# smart-bike-light.net
KiCad netlist of a schematic drawn in EAGLE
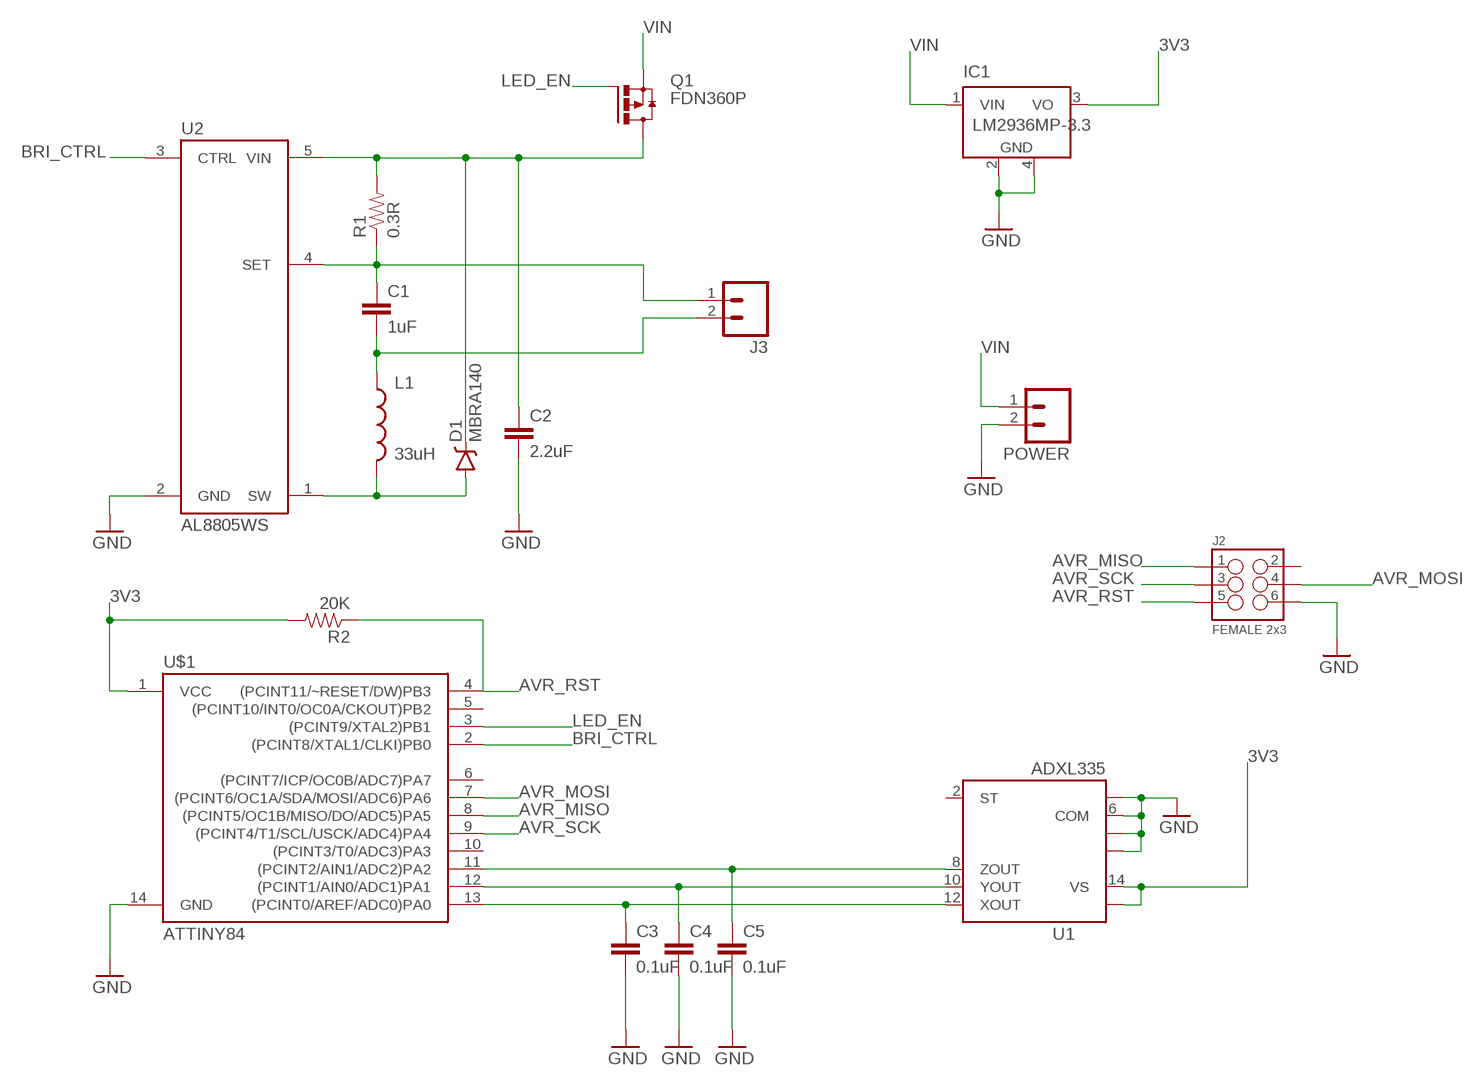
[diagram p0: schematic, sheet 1]

(export (version "E")
  (design (tool "Eeschema 10.0.6"))
  (components
    (comp (ref "C1")
      (value "1uF")
      (footprint "eagle-import:0603-CAP")
      (libsource (lib "eagle-import") (part "CAP0603-CAP"))
    )
    (comp (ref "C2")
      (value "2.2uF")
      (footprint "eagle-import:0603-CAP")
      (libsource (lib "eagle-import") (part "CAP0603-CAP"))
    )
    (comp (ref "C3")
      (value "0.1uF")
      (footprint "eagle-import:0603-CAP")
      (libsource (lib "eagle-import") (part "0.1UF-25V-5%(0603)"))
    )
    (comp (ref "C4")
      (value "0.1uF")
      (footprint "eagle-import:0603-CAP")
      (libsource (lib "eagle-import") (part "0.1UF-25V-5%(0603)"))
    )
    (comp (ref "C5")
      (value "0.1uF")
      (footprint "eagle-import:0603-CAP")
      (libsource (lib "eagle-import") (part "0.1UF-25V-5%(0603)"))
    )
    (comp (ref "D1")
      (value "MBRA140")
      (footprint "eagle-import:SMA-DIODE")
      (libsource (lib "eagle-import") (part "MBRA140"))
    )
    (comp (ref "IC1")
      (value "LM2936MP-3.3")
      (footprint "eagle-import:SOT223")
      (fields (field (name "MF") "NATIONAL SEMICONDUCTOR") (field (name "MPN") "LM2936MP-3.3/NOPB"))
      (libsource (lib "eagle-import") (part "LM2936MP?-3.3"))
    )
    (comp (ref "J2")
      (value "FEMALE 2x3")
      (footprint "eagle-import:2X3")
      (libsource (lib "eagle-import") (part "M03X2FEMALE"))
    )
    (comp (ref "J3")
      (value "M02PTH")
      (footprint "eagle-import:1X02")
      (libsource (lib "eagle-import") (part "M02PTH"))
    )
    (comp (ref "L1")
      (value "33uH")
      (footprint "eagle-import:SRN6045")
      (libsource (lib "eagle-import") (part "INDUCTORBOURNS_SRN6045"))
    )
    (comp (ref "POWER")
      (value "M02PTH")
      (footprint "eagle-import:1X02")
      (libsource (lib "eagle-import") (part "M02PTH"))
    )
    (comp (ref "Q1")
      (value "FDN360P")
      (footprint "eagle-import:SUPER-SOT3")
      (libsource (lib "eagle-import") (part "FDN360P"))
    )
    (comp (ref "R1")
      (value "0.3R")
      (footprint "eagle-import:0603-RES")
      (libsource (lib "eagle-import") (part "RESISTOR0603"))
    )
    (comp (ref "R2")
      (value "20K")
      (footprint "eagle-import:0603-RES")
      (libsource (lib "eagle-import") (part "RESISTOR0603"))
    )
    (comp (ref "U$1")
      (value "ATTINY84")
      (footprint "eagle-import:SO14")
      (libsource (lib "eagle-import") (part "ATTINY84"))
    )
    (comp (ref "U1")
      (value "ADXL335")
      (footprint "eagle-import:LFCSP-16")
      (libsource (lib "eagle-import") (part "ADXL335"))
    )
    (comp (ref "U2")
      (value "AL8805WS")
      (footprint "eagle-import:SOT23-5")
      (libsource (lib "eagle-import") (part "AL8805"))
    )
  )
  (nets
    (net (code "1") (name "/3V3") (class "Default")
      (node (ref "IC1") (pin "3") (pinfunction "VO_3") (pintype "passive"))
      (node (ref "R2") (pin "2") (pinfunction "2_2") (pintype "passive"))
      (node (ref "U$1") (pin "1") (pinfunction "VCC_1") (pintype "bidirectional"))
      (node (ref "U1") (pin "14") (pinfunction "VS_14") (pintype "bidirectional"))
      (node (ref "U1") (pin "15") (pinfunction "VS_15") (pintype "bidirectional"))
    )
    (net (code "2") (name "/AVR_MISO") (class "Default")
      (node (ref "J2") (pin "1") (pinfunction "1_1") (pintype "bidirectional"))
      (node (ref "U$1") (pin "8") (pinfunction "(PCINT5/OC1B/MISO/DO/ADC5)PA5_8") (pintype "bidirectional"))
    )
    (net (code "3") (name "/AVR_MOSI") (class "Default")
      (node (ref "J2") (pin "4") (pinfunction "4_4") (pintype "bidirectional"))
      (node (ref "U$1") (pin "7") (pinfunction "(PCINT6/OC1A/SDA/MOSI/ADC6)PA6_7") (pintype "bidirectional"))
    )
    (net (code "4") (name "/AVR_RST") (class "Default")
      (node (ref "J2") (pin "5") (pinfunction "5_5") (pintype "bidirectional"))
      (node (ref "R2") (pin "1") (pinfunction "1_1") (pintype "passive"))
      (node (ref "U$1") (pin "4") (pinfunction "(PCINT11/~{RESET/DW})PB3_4") (pintype "bidirectional"))
    )
    (net (code "5") (name "/AVR_SCK") (class "Default")
      (node (ref "J2") (pin "3") (pinfunction "3_3") (pintype "bidirectional"))
      (node (ref "U$1") (pin "9") (pinfunction "(PCINT4/T1/SCL/USCK/ADC4)PA4_9") (pintype "bidirectional"))
    )
    (net (code "6") (name "/BRI_CTRL") (class "Default")
      (node (ref "U$1") (pin "2") (pinfunction "(PCINT8/XTAL1/CLKI)PB0_2") (pintype "bidirectional"))
      (node (ref "U2") (pin "3") (pinfunction "CTRL_3") (pintype "bidirectional"))
    )
    (net (code "7") (name "/LED_EN") (class "Default")
      (node (ref "Q1") (pin "1") (pinfunction "G_1") (pintype "passive"))
      (node (ref "U$1") (pin "3") (pinfunction "(PCINT9/XTAL2)PB1_3") (pintype "bidirectional"))
    )
    (net (code "8") (name "/VIN") (class "Default")
      (node (ref "IC1") (pin "1") (pinfunction "VIN_1") (pintype "input"))
      (node (ref "POWER") (pin "1") (pinfunction "1_1") (pintype "passive"))
      (node (ref "Q1") (pin "2") (pinfunction "S_2") (pintype "passive"))
    )
    (net (code "9") (name "GND") (class "Default")
      (node (ref "C2") (pin "2") (pinfunction "2_2") (pintype "passive"))
      (node (ref "C3") (pin "2") (pinfunction "2_2") (pintype "passive"))
      (node (ref "C4") (pin "2") (pinfunction "2_2") (pintype "passive"))
      (node (ref "C5") (pin "2") (pinfunction "2_2") (pintype "passive"))
      (node (ref "IC1") (pin "2") (pinfunction "GND_2") (pintype "passive"))
      (node (ref "IC1") (pin "4") (pinfunction "GND_4") (pintype "passive"))
      (node (ref "J2") (pin "6") (pinfunction "6_6") (pintype "bidirectional"))
      (node (ref "POWER") (pin "2") (pinfunction "2_2") (pintype "passive"))
      (node (ref "U$1") (pin "14") (pinfunction "GND_14") (pintype "bidirectional"))
      (node (ref "U1") (pin "3") (pinfunction "COM_3") (pintype "bidirectional"))
      (node (ref "U1") (pin "5") (pinfunction "COM_5") (pintype "bidirectional"))
      (node (ref "U1") (pin "6") (pinfunction "COM_6") (pintype "bidirectional"))
      (node (ref "U1") (pin "7") (pinfunction "COM_7") (pintype "bidirectional"))
      (node (ref "U2") (pin "2") (pinfunction "GND_2") (pintype "bidirectional"))
    )
    (net (code "10") (name "Net-(C1-Pad2)") (class "Default")
      (node (ref "C1") (pin "2") (pinfunction "2_2") (pintype "passive"))
      (node (ref "J3") (pin "2") (pinfunction "2_2") (pintype "passive"))
      (node (ref "L1") (pin "1") (pinfunction "1_1") (pintype "passive"))
    )
    (net (code "11") (name "Net-(Q1-D)") (class "Default")
      (node (ref "C2") (pin "1") (pinfunction "1_1") (pintype "passive"))
      (node (ref "D1") (pin "C") (pinfunction "C_C") (pintype "passive"))
      (node (ref "Q1") (pin "3") (pinfunction "D_3") (pintype "passive"))
      (node (ref "R1") (pin "2") (pinfunction "2_2") (pintype "passive"))
      (node (ref "U2") (pin "5") (pinfunction "VIN_5") (pintype "bidirectional"))
    )
    (net (code "12") (name "Net-(U$1-(PCINT0{slash}AREF{slash}ADC0)PA0)") (class "Default")
      (node (ref "C3") (pin "1") (pinfunction "1_1") (pintype "passive"))
      (node (ref "U$1") (pin "13") (pinfunction "(PCINT0/AREF/ADC0)PA0_13") (pintype "bidirectional"))
      (node (ref "U1") (pin "12") (pinfunction "XOUT_12") (pintype "bidirectional"))
    )
    (net (code "13") (name "Net-(U$1-(PCINT1{slash}AIN0{slash}ADC1)PA1)") (class "Default")
      (node (ref "C4") (pin "1") (pinfunction "1_1") (pintype "passive"))
      (node (ref "U$1") (pin "12") (pinfunction "(PCINT1/AIN0/ADC1)PA1_12") (pintype "bidirectional"))
      (node (ref "U1") (pin "10") (pinfunction "YOUT_10") (pintype "bidirectional"))
    )
    (net (code "14") (name "Net-(U$1-(PCINT2{slash}AIN1{slash}ADC2)PA2)") (class "Default")
      (node (ref "C5") (pin "1") (pinfunction "1_1") (pintype "passive"))
      (node (ref "U$1") (pin "11") (pinfunction "(PCINT2/AIN1/ADC2)PA2_11") (pintype "bidirectional"))
      (node (ref "U1") (pin "8") (pinfunction "ZOUT_8") (pintype "bidirectional"))
    )
    (net (code "15") (name "Net-(U2-SET)") (class "Default")
      (node (ref "C1") (pin "1") (pinfunction "1_1") (pintype "passive"))
      (node (ref "J3") (pin "1") (pinfunction "1_1") (pintype "passive"))
      (node (ref "R1") (pin "1") (pinfunction "1_1") (pintype "passive"))
      (node (ref "U2") (pin "4") (pinfunction "SET_4") (pintype "bidirectional"))
    )
    (net (code "16") (name "Net-(U2-SW)") (class "Default")
      (node (ref "D1") (pin "A") (pinfunction "A_A") (pintype "passive"))
      (node (ref "L1") (pin "2") (pinfunction "2_2") (pintype "passive"))
      (node (ref "U2") (pin "1") (pinfunction "SW_1") (pintype "bidirectional"))
    )
    (net (code "17") (name "unconnected-(J2-Pad2)") (class "Default")
      (node (ref "J2") (pin "2") (pinfunction "2_2") (pintype "bidirectional"))
    )
    (net (code "18") (name "unconnected-(U$1-(PCINT3{slash}T0{slash}ADC3)PA3-Pad10)") (class "Default")
      (node (ref "U$1") (pin "10") (pinfunction "(PCINT3/T0/ADC3)PA3_10") (pintype "bidirectional"))
    )
    (net (code "19") (name "unconnected-(U$1-(PCINT7{slash}ICP{slash}OC0B{slash}ADC7)PA7-Pad6)") (class "Default")
      (node (ref "U$1") (pin "6") (pinfunction "(PCINT7/ICP/OC0B/ADC7)PA7_6") (pintype "bidirectional"))
    )
    (net (code "20") (name "unconnected-(U$1-(PCINT10{slash}INT0{slash}OC0A{slash}CKOUT)PB2-Pad5)") (class "Default")
      (node (ref "U$1") (pin "5") (pinfunction "(PCINT10/INT0/OC0A/CKOUT)PB2_5") (pintype "bidirectional"))
    )
    (net (code "21") (name "unconnected-(U1-ST-Pad2)") (class "Default")
      (node (ref "U1") (pin "2") (pinfunction "ST_2") (pintype "bidirectional"))
    )
  )
)
